# lps331-adapt.net
KiCad netlist of a schematic drawn in EAGLE
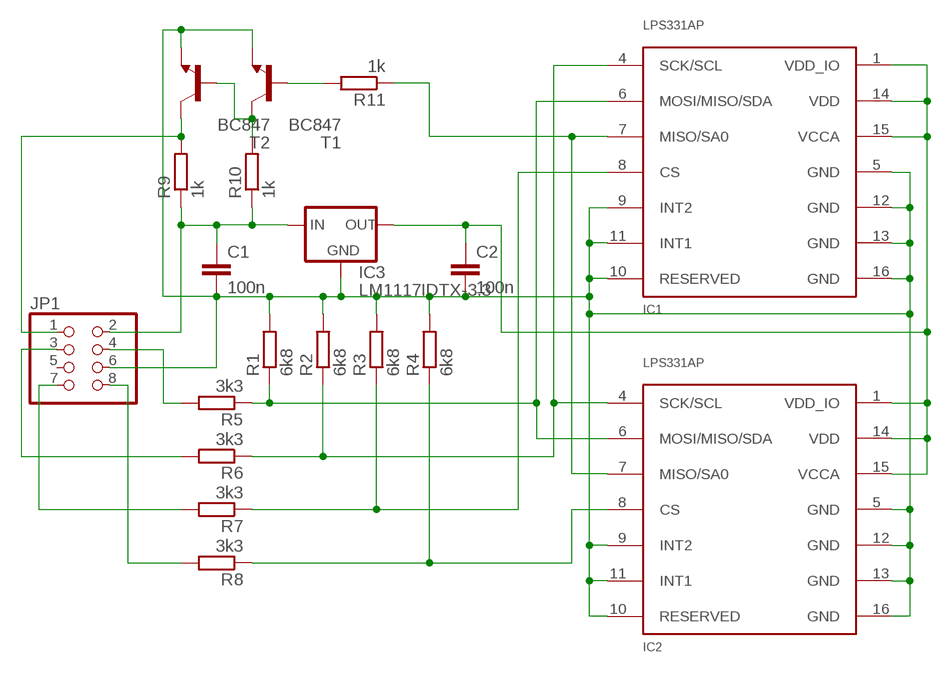
[diagram p0: schematic, sheet 1]

(export (version "E")
  (design (tool "Eeschema 10.0.6"))
  (components
    (comp (ref "C1")
      (value "100n")
      (footprint "eagle-import:C1206")
      (libsource (lib "eagle-import") (part "C-EUC1206"))
    )
    (comp (ref "C2")
      (value "100n")
      (footprint "eagle-import:C1206")
      (libsource (lib "eagle-import") (part "C-EUC1206"))
    )
    (comp (ref "IC1")
      (value "LPS331AP")
      (footprint "eagle-import:HCLGA-16L")
      (libsource (lib "eagle-import") (part "LPS331AP"))
    )
    (comp (ref "IC2")
      (value "LPS331AP")
      (footprint "eagle-import:HCLGA-16L")
      (libsource (lib "eagle-import") (part "LPS331AP"))
    )
    (comp (ref "IC3")
      (value "LM1117IDTX-3.3")
      (footprint "eagle-import:TO252")
      (libsource (lib "eagle-import") (part "LM1117IDTX-3.3"))
    )
    (comp (ref "JP1")
      (value "PINHD-2X4")
      (footprint "eagle-import:2X04")
      (libsource (lib "eagle-import") (part "PINHD-2X4"))
    )
    (comp (ref "R1")
      (value "6k8")
      (footprint "eagle-import:R1206")
      (libsource (lib "eagle-import") (part "R-EU_R1206"))
    )
    (comp (ref "R2")
      (value "6k8")
      (footprint "eagle-import:R1206")
      (libsource (lib "eagle-import") (part "R-EU_R1206"))
    )
    (comp (ref "R3")
      (value "6k8")
      (footprint "eagle-import:R1206")
      (libsource (lib "eagle-import") (part "R-EU_R1206"))
    )
    (comp (ref "R4")
      (value "6k8")
      (footprint "eagle-import:R1206")
      (libsource (lib "eagle-import") (part "R-EU_R1206"))
    )
    (comp (ref "R5")
      (value "3k3")
      (footprint "eagle-import:R1206")
      (libsource (lib "eagle-import") (part "R-EU_R1206"))
    )
    (comp (ref "R6")
      (value "3k3")
      (footprint "eagle-import:R1206")
      (libsource (lib "eagle-import") (part "R-EU_R1206"))
    )
    (comp (ref "R7")
      (value "3k3")
      (footprint "eagle-import:R1206")
      (libsource (lib "eagle-import") (part "R-EU_R1206"))
    )
    (comp (ref "R8")
      (value "3k3")
      (footprint "eagle-import:R1206")
      (libsource (lib "eagle-import") (part "R-EU_R1206"))
    )
    (comp (ref "R9")
      (value "1k")
      (footprint "eagle-import:R1206")
      (libsource (lib "eagle-import") (part "R-EU_R1206"))
    )
    (comp (ref "R10")
      (value "1k")
      (footprint "eagle-import:R1206")
      (libsource (lib "eagle-import") (part "R-EU_R1206"))
    )
    (comp (ref "R11")
      (value "1k")
      (footprint "eagle-import:R1206")
      (libsource (lib "eagle-import") (part "R-EU_R1206"))
    )
    (comp (ref "T1")
      (value "BC847")
      (footprint "eagle-import:SOT23")
      (libsource (lib "eagle-import") (part "BC847"))
    )
    (comp (ref "T2")
      (value "BC847")
      (footprint "eagle-import:SOT23")
      (libsource (lib "eagle-import") (part "BC847"))
    )
  )
  (nets
    (net (code "1") (name "Net-(IC1-CS)") (class "Default")
      (node (ref "IC1") (pin "8") (pinfunction "CS_8") (pintype "input"))
      (node (ref "R3") (pin "1") (pinfunction "1_1") (pintype "passive"))
      (node (ref "R7") (pin "1") (pinfunction "1_1") (pintype "passive"))
    )
    (net (code "2") (name "Net-(IC1-INT1)") (class "Default")
      (node (ref "C1") (pin "2") (pinfunction "2_2") (pintype "passive"))
      (node (ref "C2") (pin "2") (pinfunction "2_2") (pintype "passive"))
      (node (ref "IC1") (pin "10") (pinfunction "RESERVED_10") (pintype "input"))
      (node (ref "IC1") (pin "11") (pinfunction "INT1_11") (pintype "output"))
      (node (ref "IC1") (pin "12") (pinfunction "GND_12") (pintype "power_in"))
      (node (ref "IC1") (pin "13") (pinfunction "GND_13") (pintype "power_in"))
      (node (ref "IC1") (pin "16") (pinfunction "GND_16") (pintype "power_in"))
      (node (ref "IC1") (pin "5") (pinfunction "GND_5") (pintype "power_in"))
      (node (ref "IC1") (pin "9") (pinfunction "INT2_9") (pintype "output"))
      (node (ref "IC2") (pin "10") (pinfunction "RESERVED_10") (pintype "input"))
      (node (ref "IC2") (pin "11") (pinfunction "INT1_11") (pintype "output"))
      (node (ref "IC2") (pin "12") (pinfunction "GND_12") (pintype "power_in"))
      (node (ref "IC2") (pin "13") (pinfunction "GND_13") (pintype "power_in"))
      (node (ref "IC2") (pin "16") (pinfunction "GND_16") (pintype "power_in"))
      (node (ref "IC2") (pin "5") (pinfunction "GND_5") (pintype "power_in"))
      (node (ref "IC2") (pin "9") (pinfunction "INT2_9") (pintype "output"))
      (node (ref "IC3") (pin "1") (pinfunction "GND_1") (pintype "input"))
      (node (ref "JP1") (pin "6") (pinfunction "6_6") (pintype "passive"))
      (node (ref "R1") (pin "2") (pinfunction "2_2") (pintype "passive"))
      (node (ref "R2") (pin "2") (pinfunction "2_2") (pintype "passive"))
      (node (ref "R3") (pin "2") (pinfunction "2_2") (pintype "passive"))
      (node (ref "R4") (pin "2") (pinfunction "2_2") (pintype "passive"))
      (node (ref "T1") (pin "2") (pinfunction "E_2") (pintype "passive"))
      (node (ref "T2") (pin "2") (pinfunction "E_2") (pintype "passive"))
    )
    (net (code "3") (name "Net-(IC1-MISO{slash}SA0)") (class "Default")
      (node (ref "IC1") (pin "7") (pinfunction "MISO/SA0_7") (pintype "output"))
      (node (ref "IC2") (pin "7") (pinfunction "MISO/SA0_7") (pintype "output"))
      (node (ref "R11") (pin "1") (pinfunction "1_1") (pintype "passive"))
    )
    (net (code "4") (name "Net-(IC1-MOSI{slash}MISO{slash}SDA)") (class "Default")
      (node (ref "IC1") (pin "6") (pinfunction "MOSI/MISO/SDA_6") (pintype "bidirectional"))
      (node (ref "IC2") (pin "6") (pinfunction "MOSI/MISO/SDA_6") (pintype "bidirectional"))
      (node (ref "R1") (pin "1") (pinfunction "1_1") (pintype "passive"))
      (node (ref "R5") (pin "1") (pinfunction "1_1") (pintype "passive"))
    )
    (net (code "5") (name "Net-(IC1-SCK{slash}SCL)") (class "Default")
      (node (ref "IC1") (pin "4") (pinfunction "SCK/SCL_4") (pintype "input"))
      (node (ref "IC2") (pin "4") (pinfunction "SCK/SCL_4") (pintype "input"))
      (node (ref "R2") (pin "1") (pinfunction "1_1") (pintype "passive"))
      (node (ref "R6") (pin "1") (pinfunction "1_1") (pintype "passive"))
    )
    (net (code "6") (name "Net-(IC1-VCCA)") (class "Default")
      (node (ref "C2") (pin "1") (pinfunction "1_1") (pintype "passive"))
      (node (ref "IC1") (pin "1") (pinfunction "VDD_IO_1") (pintype "power_in"))
      (node (ref "IC1") (pin "14") (pinfunction "VDD_14") (pintype "power_in"))
      (node (ref "IC1") (pin "15") (pinfunction "VCCA_15") (pintype "power_in"))
      (node (ref "IC2") (pin "1") (pinfunction "VDD_IO_1") (pintype "power_in"))
      (node (ref "IC2") (pin "14") (pinfunction "VDD_14") (pintype "power_in"))
      (node (ref "IC2") (pin "15") (pinfunction "VCCA_15") (pintype "power_in"))
      (node (ref "IC3") (pin "TAB") (pinfunction "OUT_TAB") (pintype "passive"))
    )
    (net (code "7") (name "Net-(IC2-CS)") (class "Default")
      (node (ref "IC2") (pin "8") (pinfunction "CS_8") (pintype "input"))
      (node (ref "R4") (pin "1") (pinfunction "1_1") (pintype "passive"))
      (node (ref "R8") (pin "1") (pinfunction "1_1") (pintype "passive"))
    )
    (net (code "8") (name "Net-(IC3-IN)") (class "Default")
      (node (ref "C1") (pin "1") (pinfunction "1_1") (pintype "passive"))
      (node (ref "IC3") (pin "2") (pinfunction "IN_2") (pintype "input"))
      (node (ref "JP1") (pin "2") (pinfunction "2_2") (pintype "passive"))
      (node (ref "R10") (pin "1") (pinfunction "1_1") (pintype "passive"))
      (node (ref "R9") (pin "1") (pinfunction "1_1") (pintype "passive"))
    )
    (net (code "9") (name "Net-(JP1-Pad3)") (class "Default")
      (node (ref "JP1") (pin "3") (pinfunction "3_3") (pintype "passive"))
      (node (ref "R6") (pin "2") (pinfunction "2_2") (pintype "passive"))
    )
    (net (code "10") (name "Net-(JP1-Pad4)") (class "Default")
      (node (ref "JP1") (pin "4") (pinfunction "4_4") (pintype "passive"))
      (node (ref "R5") (pin "2") (pinfunction "2_2") (pintype "passive"))
    )
    (net (code "11") (name "Net-(JP1-Pad7)") (class "Default")
      (node (ref "JP1") (pin "7") (pinfunction "7_7") (pintype "passive"))
      (node (ref "R7") (pin "2") (pinfunction "2_2") (pintype "passive"))
    )
    (net (code "12") (name "Net-(JP1-Pad8)") (class "Default")
      (node (ref "JP1") (pin "8") (pinfunction "8_8") (pintype "passive"))
      (node (ref "R8") (pin "2") (pinfunction "2_2") (pintype "passive"))
    )
    (net (code "13") (name "Net-(T1-B)") (class "Default")
      (node (ref "R11") (pin "2") (pinfunction "2_2") (pintype "passive"))
      (node (ref "T1") (pin "1") (pinfunction "B_1") (pintype "passive"))
    )
    (net (code "14") (name "Net-(T1-C)") (class "Default")
      (node (ref "R10") (pin "2") (pinfunction "2_2") (pintype "passive"))
      (node (ref "T1") (pin "3") (pinfunction "C_3") (pintype "passive"))
      (node (ref "T2") (pin "1") (pinfunction "B_1") (pintype "passive"))
    )
    (net (code "15") (name "Net-(T2-C)") (class "Default")
      (node (ref "JP1") (pin "1") (pinfunction "1_1") (pintype "passive"))
      (node (ref "R9") (pin "2") (pinfunction "2_2") (pintype "passive"))
      (node (ref "T2") (pin "3") (pinfunction "C_3") (pintype "passive"))
    )
    (net (code "16") (name "unconnected-(JP1-Pad5)") (class "Default")
      (node (ref "JP1") (pin "5") (pinfunction "5_5") (pintype "passive"))
    )
  )
)
